# pico_test_synth1.net
KiCad netlist of a schematic drawn in EAGLE
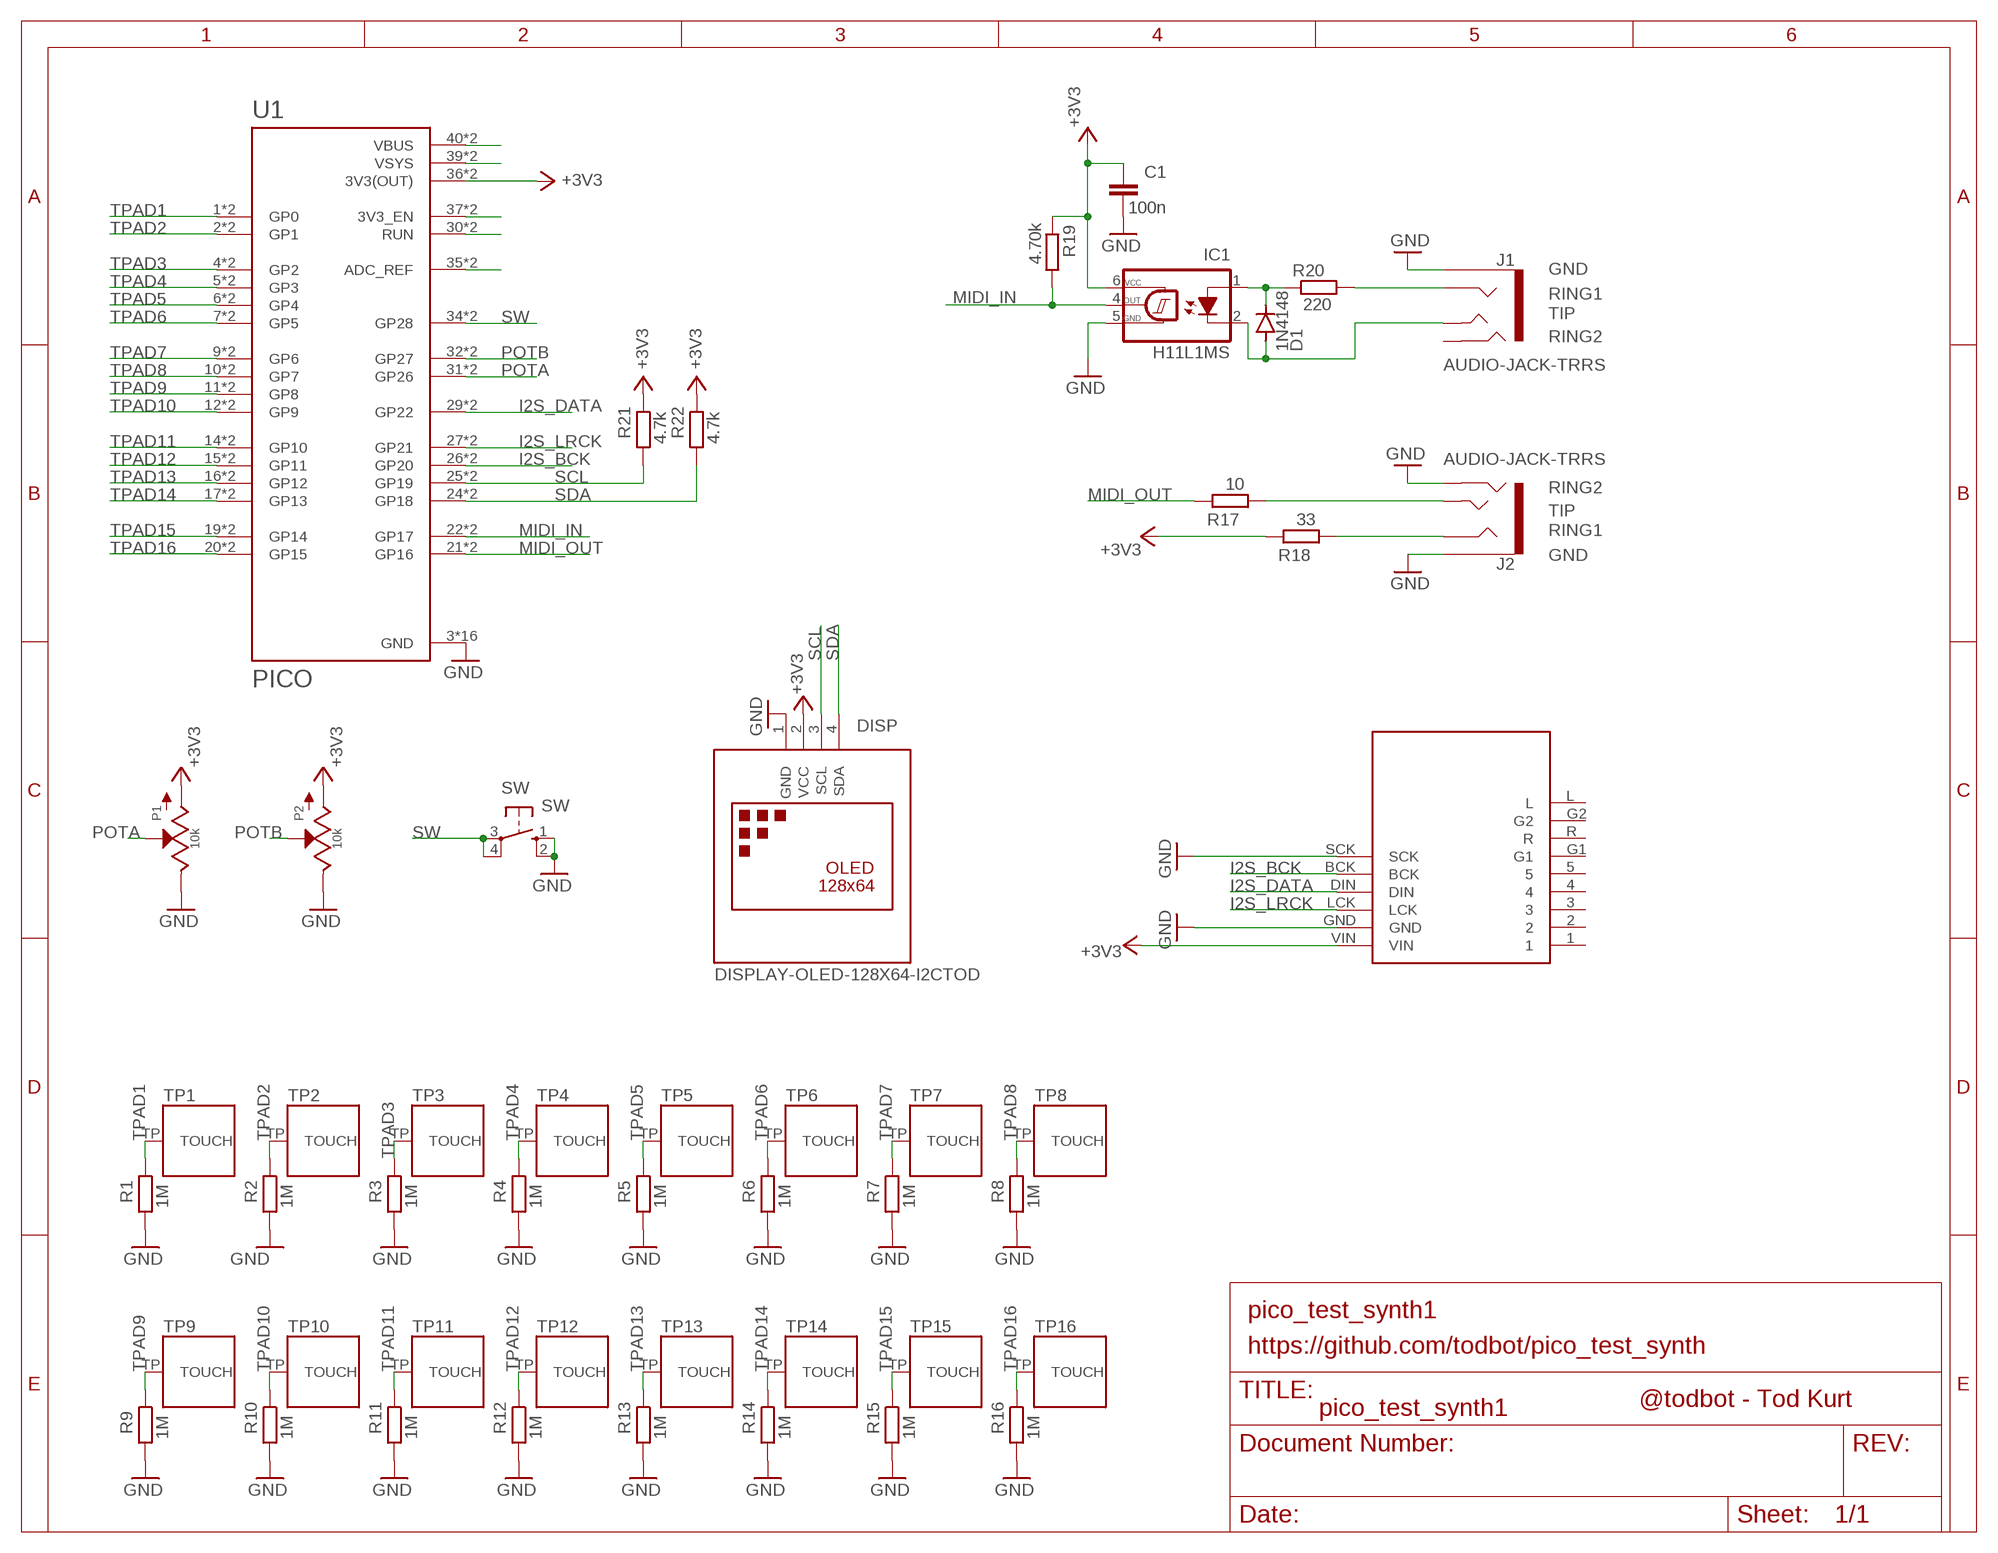
[diagram p0: schematic, sheet 1]

(export (version "E")
  (design (tool "Eeschema 10.0.6"))
  (components
    (comp (ref "C1")
      (value "100n")
      (footprint "eagle-import:C0805")
      (libsource (lib "eagle-import") (part "C-EUC0805"))
    )
    (comp (ref "D1")
      (value "1N4148")
      (footprint "eagle-import:SOD123")
      (libsource (lib "eagle-import") (part "DIODE-SOD123"))
    )
    (comp (ref "DISP")
      (value "DISPLAY-OLED-128X64-I2CTOD")
      (footprint "eagle-import:DISPLAY-OLED-128X64-I2C-TOD")
      (libsource (lib "eagle-import") (part "DISPLAY-OLED-128X64-I2CTOD"))
    )
    (comp (ref "IC1")
      (value "H11L1MS")
      (footprint "eagle-import:DIL6-SMD")
      (libsource (lib "eagle-import") (part "H11LMS1"))
    )
    (comp (ref "J1")
      (value "AUDIO-JACK-TRRS")
      (footprint "eagle-import:PJ-320D_SPARKFUN")
      (fields (field (name "MPN") "PJ-320D"))
      (libsource (lib "eagle-import") (part "AUDIO-JACK-TRRS"))
    )
    (comp (ref "J2")
      (value "AUDIO-JACK-TRRS")
      (footprint "eagle-import:PJ-320D_SPARKFUN")
      (fields (field (name "MPN") "PJ-320D") (field (name "LCSC") "C431535"))
      (libsource (lib "eagle-import") (part "AUDIO-JACK-TRRS"))
    )
    (comp (ref "P1")
      (value "10k")
      (footprint "eagle-import:OG-POTS_ALPS_POT_VERTICAL_WITHBIGKNOB")
      (libsource (lib "eagle-import") (part "POTZEPHPOT_BIGKNOB"))
    )
    (comp (ref "P2")
      (value "10k")
      (footprint "eagle-import:OG-POTS_ALPS_POT_VERTICAL_WITHBIGKNOB")
      (libsource (lib "eagle-import") (part "POTZEPHPOT_BIGKNOB"))
    )
    (comp (ref "R1")
      (value "1M")
      (footprint "eagle-import:R0805")
      (libsource (lib "eagle-import") (part "R-EU_R0805"))
    )
    (comp (ref "R2")
      (value "1M")
      (footprint "eagle-import:R0805")
      (libsource (lib "eagle-import") (part "R-EU_R0805"))
    )
    (comp (ref "R3")
      (value "1M")
      (footprint "eagle-import:R0805")
      (libsource (lib "eagle-import") (part "R-EU_R0805"))
    )
    (comp (ref "R4")
      (value "1M")
      (footprint "eagle-import:R0805")
      (libsource (lib "eagle-import") (part "R-EU_R0805"))
    )
    (comp (ref "R5")
      (value "1M")
      (footprint "eagle-import:R0805")
      (libsource (lib "eagle-import") (part "R-EU_R0805"))
    )
    (comp (ref "R6")
      (value "1M")
      (footprint "eagle-import:R0805")
      (libsource (lib "eagle-import") (part "R-EU_R0805"))
    )
    (comp (ref "R7")
      (value "1M")
      (footprint "eagle-import:R0805")
      (libsource (lib "eagle-import") (part "R-EU_R0805"))
    )
    (comp (ref "R8")
      (value "1M")
      (footprint "eagle-import:R0805")
      (libsource (lib "eagle-import") (part "R-EU_R0805"))
    )
    (comp (ref "R9")
      (value "1M")
      (footprint "eagle-import:R0805")
      (libsource (lib "eagle-import") (part "R-EU_R0805"))
    )
    (comp (ref "R10")
      (value "1M")
      (footprint "eagle-import:R0805")
      (libsource (lib "eagle-import") (part "R-EU_R0805"))
    )
    (comp (ref "R11")
      (value "1M")
      (footprint "eagle-import:R0805")
      (libsource (lib "eagle-import") (part "R-EU_R0805"))
    )
    (comp (ref "R12")
      (value "1M")
      (footprint "eagle-import:R0805")
      (libsource (lib "eagle-import") (part "R-EU_R0805"))
    )
    (comp (ref "R13")
      (value "1M")
      (footprint "eagle-import:R0805")
      (libsource (lib "eagle-import") (part "R-EU_R0805"))
    )
    (comp (ref "R14")
      (value "1M")
      (footprint "eagle-import:R0805")
      (libsource (lib "eagle-import") (part "R-EU_R0805"))
    )
    (comp (ref "R15")
      (value "1M")
      (footprint "eagle-import:R0805")
      (libsource (lib "eagle-import") (part "R-EU_R0805"))
    )
    (comp (ref "R16")
      (value "1M")
      (footprint "eagle-import:R0805")
      (libsource (lib "eagle-import") (part "R-EU_R0805"))
    )
    (comp (ref "R17")
      (value "10")
      (footprint "eagle-import:R0805")
      (libsource (lib "eagle-import") (part "R-EU_R0805"))
    )
    (comp (ref "R18")
      (value "33")
      (footprint "eagle-import:R0805")
      (libsource (lib "eagle-import") (part "R-EU_R0805"))
    )
    (comp (ref "R19")
      (value "4.70k")
      (footprint "eagle-import:R0805")
      (libsource (lib "eagle-import") (part "R-EU_R0805"))
    )
    (comp (ref "R20")
      (value "220")
      (footprint "eagle-import:R0805")
      (libsource (lib "eagle-import") (part "R-EU_R0805"))
    )
    (comp (ref "R21")
      (value "4.7k")
      (footprint "eagle-import:R0805")
      (libsource (lib "eagle-import") (part "R-EU_R0805"))
    )
    (comp (ref "R22")
      (value "4.7k")
      (footprint "eagle-import:R0805")
      (libsource (lib "eagle-import") (part "R-EU_R0805"))
    )
    (comp (ref "SW")
      (value "SW")
      (footprint "eagle-import:B3F-10XX")
      (fields (field (name "MPN") "B3F-1000"))
      (libsource (lib "eagle-import") (part "10-XX"))
    )
    (comp (ref "TP1")
      (value "TOUCHPADA")
      (footprint "eagle-import:TOUCHPADA_0.5IN")
      (libsource (lib "eagle-import") (part "TOUCHPADA"))
    )
    (comp (ref "TP2")
      (value "TOUCHPADA")
      (footprint "eagle-import:TOUCHPADA_0.5IN")
      (libsource (lib "eagle-import") (part "TOUCHPADA"))
    )
    (comp (ref "TP3")
      (value "TOUCHPADA")
      (footprint "eagle-import:TOUCHPADA_0.5IN")
      (libsource (lib "eagle-import") (part "TOUCHPADA"))
    )
    (comp (ref "TP4")
      (value "TOUCHPADA")
      (footprint "eagle-import:TOUCHPADA_0.5IN")
      (libsource (lib "eagle-import") (part "TOUCHPADA"))
    )
    (comp (ref "TP5")
      (value "TOUCHPADA")
      (footprint "eagle-import:TOUCHPADA_0.5IN")
      (libsource (lib "eagle-import") (part "TOUCHPADA"))
    )
    (comp (ref "TP6")
      (value "TOUCHPADA")
      (footprint "eagle-import:TOUCHPADA_0.5IN")
      (libsource (lib "eagle-import") (part "TOUCHPADA"))
    )
    (comp (ref "TP7")
      (value "TOUCHPADA")
      (footprint "eagle-import:TOUCHPADA_0.5IN")
      (libsource (lib "eagle-import") (part "TOUCHPADA"))
    )
    (comp (ref "TP8")
      (value "TOUCHPADA")
      (footprint "eagle-import:TOUCHPADA_0.5IN")
      (libsource (lib "eagle-import") (part "TOUCHPADA"))
    )
    (comp (ref "TP9")
      (value "TOUCHPADA")
      (footprint "eagle-import:TOUCHPADA_0.5IN")
      (libsource (lib "eagle-import") (part "TOUCHPADA"))
    )
    (comp (ref "TP10")
      (value "TOUCHPADA")
      (footprint "eagle-import:TOUCHPADA_0.5IN")
      (libsource (lib "eagle-import") (part "TOUCHPADA"))
    )
    (comp (ref "TP11")
      (value "TOUCHPADA")
      (footprint "eagle-import:TOUCHPADA_0.5IN")
      (libsource (lib "eagle-import") (part "TOUCHPADA"))
    )
    (comp (ref "TP12")
      (value "TOUCHPADA")
      (footprint "eagle-import:TOUCHPADA_0.5IN")
      (libsource (lib "eagle-import") (part "TOUCHPADA"))
    )
    (comp (ref "TP13")
      (value "TOUCHPADA")
      (footprint "eagle-import:TOUCHPADA_0.5IN")
      (libsource (lib "eagle-import") (part "TOUCHPADA"))
    )
    (comp (ref "TP14")
      (value "TOUCHPADA")
      (footprint "eagle-import:TOUCHPADA_0.5IN")
      (libsource (lib "eagle-import") (part "TOUCHPADA"))
    )
    (comp (ref "TP15")
      (value "TOUCHPADA")
      (footprint "eagle-import:TOUCHPADA_0.5IN")
      (libsource (lib "eagle-import") (part "TOUCHPADA"))
    )
    (comp (ref "TP16")
      (value "TOUCHPADA")
      (footprint "eagle-import:TOUCHPADA_0.5IN")
      (libsource (lib "eagle-import") (part "TOUCHPADA"))
    )
    (comp (ref "U1")
      (value "PICO")
      (footprint "eagle-import:PICO-PKG-NO_DEBUG")
      (libsource (lib "eagle-import") (part "RASPBERRY_PICO-NO_DEBUG"))
    )
    (comp (ref "U2")
      (value "I2S_PCM_51XX_SOUNDCARD")
      (footprint "eagle-import:I2S_PCM_5100_SOUNDCARD")
      (libsource (lib "eagle-import") (part "I2S_PCM_51XX_SOUNDCARD"))
    )
  )
  (nets
    (net (code "1") (name "+3V3") (class "Default")
      (node (ref "C1") (pin "1") (pinfunction "1_1") (pintype "passive"))
      (node (ref "DISP") (pin "2") (pinfunction "VCC_2") (pintype "power_in"))
      (node (ref "IC1") (pin "6") (pinfunction "VCC_6") (pintype "power_in"))
      (node (ref "P1") (pin "P$3") (pinfunction "A_P$3") (pintype "passive"))
      (node (ref "P2") (pin "P$3") (pinfunction "A_P$3") (pintype "passive"))
      (node (ref "R18") (pin "1") (pinfunction "1_1") (pintype "passive"))
      (node (ref "R19") (pin "1") (pinfunction "1_1") (pintype "passive"))
      (node (ref "R21") (pin "1") (pinfunction "1_1") (pintype "passive"))
      (node (ref "R22") (pin "1") (pinfunction "1_1") (pintype "passive"))
      (node (ref "U1") (pin "36") (pinfunction "3V3(OUT)_36") (pintype "power_in"))
      (node (ref "U1") (pin "P$36") (pinfunction "3V3(OUT)_P$36") (pintype "power_in"))
      (node (ref "U2") (pin "VIN") (pinfunction "VIN_VIN") (pintype "bidirectional"))
    )
    (net (code "2") (name "/I2S_BCK") (class "Default")
      (node (ref "U1") (pin "26") (pinfunction "GP20_26") (pintype "bidirectional"))
      (node (ref "U1") (pin "P$26") (pinfunction "GP20_P$26") (pintype "bidirectional"))
      (node (ref "U2") (pin "BCK") (pinfunction "BCK_BCK") (pintype "bidirectional"))
    )
    (net (code "3") (name "/I2S_DATA") (class "Default")
      (node (ref "U1") (pin "29") (pinfunction "GP22_29") (pintype "bidirectional"))
      (node (ref "U1") (pin "P$29") (pinfunction "GP22_P$29") (pintype "bidirectional"))
      (node (ref "U2") (pin "DIN") (pinfunction "DIN_DIN") (pintype "bidirectional"))
    )
    (net (code "4") (name "/I2S_LRCK") (class "Default")
      (node (ref "U1") (pin "27") (pinfunction "GP21_27") (pintype "bidirectional"))
      (node (ref "U1") (pin "P$27") (pinfunction "GP21_P$27") (pintype "bidirectional"))
      (node (ref "U2") (pin "LCK") (pinfunction "LCK_LCK") (pintype "bidirectional"))
    )
    (net (code "5") (name "/MIDI_IN") (class "Default")
      (node (ref "IC1") (pin "4") (pinfunction "OUT_4") (pintype "output"))
      (node (ref "R19") (pin "2") (pinfunction "2_2") (pintype "passive"))
      (node (ref "U1") (pin "22") (pinfunction "GP17_22") (pintype "bidirectional"))
      (node (ref "U1") (pin "P$22") (pinfunction "GP17_P$22") (pintype "bidirectional"))
    )
    (net (code "6") (name "/MIDI_OUT") (class "Default")
      (node (ref "R17") (pin "1") (pinfunction "1_1") (pintype "passive"))
      (node (ref "U1") (pin "21") (pinfunction "GP16_21") (pintype "bidirectional"))
      (node (ref "U1") (pin "P$21") (pinfunction "GP16_P$21") (pintype "bidirectional"))
    )
    (net (code "7") (name "/POTA") (class "Default")
      (node (ref "P1") (pin "P$2") (pinfunction "S_P$2") (pintype "passive"))
      (node (ref "U1") (pin "31") (pinfunction "GP26_31") (pintype "bidirectional"))
      (node (ref "U1") (pin "P$31") (pinfunction "GP26_P$31") (pintype "bidirectional"))
    )
    (net (code "8") (name "/POTB") (class "Default")
      (node (ref "P2") (pin "P$2") (pinfunction "S_P$2") (pintype "passive"))
      (node (ref "U1") (pin "32") (pinfunction "GP27_32") (pintype "bidirectional"))
      (node (ref "U1") (pin "P$32") (pinfunction "GP27_P$32") (pintype "bidirectional"))
    )
    (net (code "9") (name "/SCL") (class "Default")
      (node (ref "DISP") (pin "3") (pinfunction "SCL_3") (pintype "bidirectional"))
      (node (ref "R21") (pin "2") (pinfunction "2_2") (pintype "passive"))
      (node (ref "U1") (pin "25") (pinfunction "GP19_25") (pintype "bidirectional"))
      (node (ref "U1") (pin "P$25") (pinfunction "GP19_P$25") (pintype "bidirectional"))
    )
    (net (code "10") (name "/SDA") (class "Default")
      (node (ref "DISP") (pin "4") (pinfunction "SDA_4") (pintype "bidirectional"))
      (node (ref "R22") (pin "2") (pinfunction "2_2") (pintype "passive"))
      (node (ref "U1") (pin "24") (pinfunction "GP18_24") (pintype "bidirectional"))
      (node (ref "U1") (pin "P$24") (pinfunction "GP18_P$24") (pintype "bidirectional"))
    )
    (net (code "11") (name "/SW") (class "Default")
      (node (ref "SW") (pin "3") (pinfunction "P_3") (pintype "passive"))
      (node (ref "SW") (pin "4") (pinfunction "P1_4") (pintype "passive"))
      (node (ref "U1") (pin "34") (pinfunction "GP28_34") (pintype "bidirectional"))
      (node (ref "U1") (pin "P$34") (pinfunction "GP28_P$34") (pintype "bidirectional"))
    )
    (net (code "12") (name "/TPAD1") (class "Default")
      (node (ref "R1") (pin "1") (pinfunction "1_1") (pintype "passive"))
      (node (ref "TP1") (pin "TP") (pinfunction "TOUCH_TP") (pintype "bidirectional"))
      (node (ref "U1") (pin "1") (pinfunction "GP0_1") (pintype "bidirectional"))
      (node (ref "U1") (pin "P$1") (pinfunction "GP0_P$1") (pintype "bidirectional"))
    )
    (net (code "13") (name "/TPAD2") (class "Default")
      (node (ref "R2") (pin "1") (pinfunction "1_1") (pintype "passive"))
      (node (ref "TP2") (pin "TP") (pinfunction "TOUCH_TP") (pintype "bidirectional"))
      (node (ref "U1") (pin "2") (pinfunction "GP1_2") (pintype "bidirectional"))
      (node (ref "U1") (pin "P$2") (pinfunction "GP1_P$2") (pintype "bidirectional"))
    )
    (net (code "14") (name "/TPAD3") (class "Default")
      (node (ref "R3") (pin "1") (pinfunction "1_1") (pintype "passive"))
      (node (ref "TP3") (pin "TP") (pinfunction "TOUCH_TP") (pintype "bidirectional"))
      (node (ref "U1") (pin "4") (pinfunction "GP2_4") (pintype "bidirectional"))
      (node (ref "U1") (pin "P$4") (pinfunction "GP2_P$4") (pintype "bidirectional"))
    )
    (net (code "15") (name "/TPAD4") (class "Default")
      (node (ref "R4") (pin "1") (pinfunction "1_1") (pintype "passive"))
      (node (ref "TP4") (pin "TP") (pinfunction "TOUCH_TP") (pintype "bidirectional"))
      (node (ref "U1") (pin "5") (pinfunction "GP3_5") (pintype "bidirectional"))
      (node (ref "U1") (pin "P$5") (pinfunction "GP3_P$5") (pintype "bidirectional"))
    )
    (net (code "16") (name "/TPAD5") (class "Default")
      (node (ref "R5") (pin "1") (pinfunction "1_1") (pintype "passive"))
      (node (ref "TP5") (pin "TP") (pinfunction "TOUCH_TP") (pintype "bidirectional"))
      (node (ref "U1") (pin "6") (pinfunction "GP4_6") (pintype "bidirectional"))
      (node (ref "U1") (pin "P$6") (pinfunction "GP4_P$6") (pintype "bidirectional"))
    )
    (net (code "17") (name "/TPAD6") (class "Default")
      (node (ref "R6") (pin "1") (pinfunction "1_1") (pintype "passive"))
      (node (ref "TP6") (pin "TP") (pinfunction "TOUCH_TP") (pintype "bidirectional"))
      (node (ref "U1") (pin "7") (pinfunction "GP5_7") (pintype "bidirectional"))
      (node (ref "U1") (pin "P$7") (pinfunction "GP5_P$7") (pintype "bidirectional"))
    )
    (net (code "18") (name "/TPAD7") (class "Default")
      (node (ref "R7") (pin "1") (pinfunction "1_1") (pintype "passive"))
      (node (ref "TP7") (pin "TP") (pinfunction "TOUCH_TP") (pintype "bidirectional"))
      (node (ref "U1") (pin "9") (pinfunction "GP6_9") (pintype "bidirectional"))
      (node (ref "U1") (pin "P$9") (pinfunction "GP6_P$9") (pintype "bidirectional"))
    )
    (net (code "19") (name "/TPAD8") (class "Default")
      (node (ref "R8") (pin "1") (pinfunction "1_1") (pintype "passive"))
      (node (ref "TP8") (pin "TP") (pinfunction "TOUCH_TP") (pintype "bidirectional"))
      (node (ref "U1") (pin "10") (pinfunction "GP7_10") (pintype "bidirectional"))
      (node (ref "U1") (pin "P$10") (pinfunction "GP7_P$10") (pintype "bidirectional"))
    )
    (net (code "20") (name "/TPAD9") (class "Default")
      (node (ref "R9") (pin "1") (pinfunction "1_1") (pintype "passive"))
      (node (ref "TP9") (pin "TP") (pinfunction "TOUCH_TP") (pintype "bidirectional"))
      (node (ref "U1") (pin "11") (pinfunction "GP8_11") (pintype "bidirectional"))
      (node (ref "U1") (pin "P$11") (pinfunction "GP8_P$11") (pintype "bidirectional"))
    )
    (net (code "21") (name "/TPAD10") (class "Default")
      (node (ref "R10") (pin "1") (pinfunction "1_1") (pintype "passive"))
      (node (ref "TP10") (pin "TP") (pinfunction "TOUCH_TP") (pintype "bidirectional"))
      (node (ref "U1") (pin "12") (pinfunction "GP9_12") (pintype "bidirectional"))
      (node (ref "U1") (pin "P$12") (pinfunction "GP9_P$12") (pintype "bidirectional"))
    )
    (net (code "22") (name "/TPAD11") (class "Default")
      (node (ref "R11") (pin "1") (pinfunction "1_1") (pintype "passive"))
      (node (ref "TP11") (pin "TP") (pinfunction "TOUCH_TP") (pintype "bidirectional"))
      (node (ref "U1") (pin "14") (pinfunction "GP10_14") (pintype "bidirectional"))
      (node (ref "U1") (pin "P$14") (pinfunction "GP10_P$14") (pintype "bidirectional"))
    )
    (net (code "23") (name "/TPAD12") (class "Default")
      (node (ref "R12") (pin "1") (pinfunction "1_1") (pintype "passive"))
      (node (ref "TP12") (pin "TP") (pinfunction "TOUCH_TP") (pintype "bidirectional"))
      (node (ref "U1") (pin "15") (pinfunction "GP11_15") (pintype "bidirectional"))
      (node (ref "U1") (pin "P$15") (pinfunction "GP11_P$15") (pintype "bidirectional"))
    )
    (net (code "24") (name "/TPAD13") (class "Default")
      (node (ref "R13") (pin "1") (pinfunction "1_1") (pintype "passive"))
      (node (ref "TP13") (pin "TP") (pinfunction "TOUCH_TP") (pintype "bidirectional"))
      (node (ref "U1") (pin "16") (pinfunction "GP12_16") (pintype "bidirectional"))
      (node (ref "U1") (pin "P$16") (pinfunction "GP12_P$16") (pintype "bidirectional"))
    )
    (net (code "25") (name "/TPAD14") (class "Default")
      (node (ref "R14") (pin "1") (pinfunction "1_1") (pintype "passive"))
      (node (ref "TP14") (pin "TP") (pinfunction "TOUCH_TP") (pintype "bidirectional"))
      (node (ref "U1") (pin "17") (pinfunction "GP13_17") (pintype "bidirectional"))
      (node (ref "U1") (pin "P$17") (pinfunction "GP13_P$17") (pintype "bidirectional"))
    )
    (net (code "26") (name "/TPAD15") (class "Default")
      (node (ref "R15") (pin "1") (pinfunction "1_1") (pintype "passive"))
      (node (ref "TP15") (pin "TP") (pinfunction "TOUCH_TP") (pintype "bidirectional"))
      (node (ref "U1") (pin "19") (pinfunction "GP14_19") (pintype "bidirectional"))
      (node (ref "U1") (pin "P$19") (pinfunction "GP14_P$19") (pintype "bidirectional"))
    )
    (net (code "27") (name "/TPAD16") (class "Default")
      (node (ref "R16") (pin "1") (pinfunction "1_1") (pintype "passive"))
      (node (ref "TP16") (pin "TP") (pinfunction "TOUCH_TP") (pintype "bidirectional"))
      (node (ref "U1") (pin "20") (pinfunction "GP15_20") (pintype "bidirectional"))
      (node (ref "U1") (pin "P$20") (pinfunction "GP15_P$20") (pintype "bidirectional"))
    )
    (net (code "28") (name "GND") (class "Default")
      (node (ref "C1") (pin "2") (pinfunction "2_2") (pintype "passive"))
      (node (ref "DISP") (pin "1") (pinfunction "GND_1") (pintype "power_in"))
      (node (ref "IC1") (pin "5") (pinfunction "GND_5") (pintype "power_in"))
      (node (ref "J1") (pin "EARTH") (pinfunction "EARTH_EARTH") (pintype "bidirectional"))
      (node (ref "J2") (pin "EARTH") (pinfunction "EARTH_EARTH") (pintype "bidirectional"))
      (node (ref "J2") (pin "RING2") (pinfunction "RING2_RING2") (pintype "bidirectional"))
      (node (ref "P1") (pin "P$1") (pinfunction "E_P$1") (pintype "passive"))
      (node (ref "P2") (pin "P$1") (pinfunction "E_P$1") (pintype "passive"))
      (node (ref "R1") (pin "2") (pinfunction "2_2") (pintype "passive"))
      (node (ref "R10") (pin "2") (pinfunction "2_2") (pintype "passive"))
      (node (ref "R11") (pin "2") (pinfunction "2_2") (pintype "passive"))
      (node (ref "R12") (pin "2") (pinfunction "2_2") (pintype "passive"))
      (node (ref "R13") (pin "2") (pinfunction "2_2") (pintype "passive"))
      (node (ref "R14") (pin "2") (pinfunction "2_2") (pintype "passive"))
      (node (ref "R15") (pin "2") (pinfunction "2_2") (pintype "passive"))
      (node (ref "R16") (pin "2") (pinfunction "2_2") (pintype "passive"))
      (node (ref "R2") (pin "2") (pinfunction "2_2") (pintype "passive"))
      (node (ref "R3") (pin "2") (pinfunction "2_2") (pintype "passive"))
      (node (ref "R4") (pin "2") (pinfunction "2_2") (pintype "passive"))
      (node (ref "R5") (pin "2") (pinfunction "2_2") (pintype "passive"))
      (node (ref "R6") (pin "2") (pinfunction "2_2") (pintype "passive"))
      (node (ref "R7") (pin "2") (pinfunction "2_2") (pintype "passive"))
      (node (ref "R8") (pin "2") (pinfunction "2_2") (pintype "passive"))
      (node (ref "R9") (pin "2") (pinfunction "2_2") (pintype "passive"))
      (node (ref "SW") (pin "1") (pinfunction "S_1") (pintype "passive"))
      (node (ref "SW") (pin "2") (pinfunction "S1_2") (pintype "passive"))
      (node (ref "U1") (pin "13") (pinfunction "GND_13") (pintype "power_in"))
      (node (ref "U1") (pin "18") (pinfunction "GND_18") (pintype "power_in"))
      (node (ref "U1") (pin "23") (pinfunction "GND_23") (pintype "power_in"))
      (node (ref "U1") (pin "28") (pinfunction "GND_28") (pintype "power_in"))
      (node (ref "U1") (pin "3") (pinfunction "GND_3") (pintype "power_in"))
      (node (ref "U1") (pin "33") (pinfunction "GND_33") (pintype "power_in"))
      (node (ref "U1") (pin "38") (pinfunction "GND_38") (pintype "power_in"))
      (node (ref "U1") (pin "8") (pinfunction "GND_8") (pintype "power_in"))
      (node (ref "U1") (pin "P$13") (pinfunction "GND_P$13") (pintype "power_in"))
      (node (ref "U1") (pin "P$18") (pinfunction "GND_P$18") (pintype "power_in"))
      (node (ref "U1") (pin "P$23") (pinfunction "GND_P$23") (pintype "power_in"))
      (node (ref "U1") (pin "P$28") (pinfunction "GND_P$28") (pintype "power_in"))
      (node (ref "U1") (pin "P$3") (pinfunction "GND_P$3") (pintype "power_in"))
      (node (ref "U1") (pin "P$33") (pinfunction "GND_P$33") (pintype "power_in"))
      (node (ref "U1") (pin "P$38") (pinfunction "GND_P$38") (pintype "power_in"))
      (node (ref "U1") (pin "P$8") (pinfunction "GND_P$8") (pintype "power_in"))
      (node (ref "U2") (pin "GND") (pinfunction "GND_GND") (pintype "bidirectional"))
      (node (ref "U2") (pin "SCK") (pinfunction "SCK_SCK") (pintype "bidirectional"))
    )
    (net (code "29") (name "Net-(IC1-A)") (class "Default")
      (node (ref "D1") (pin "C") (pinfunction "C_C") (pintype "passive"))
      (node (ref "IC1") (pin "1") (pinfunction "A_1") (pintype "passive"))
      (node (ref "R20") (pin "1") (pinfunction "1_1") (pintype "passive"))
    )
    (net (code "30") (name "Net-(IC1-C)") (class "Default")
      (node (ref "D1") (pin "A") (pinfunction "A_A") (pintype "passive"))
      (node (ref "IC1") (pin "2") (pinfunction "C_2") (pintype "passive"))
      (node (ref "J1") (pin "TIP") (pinfunction "TIP_TIP") (pintype "bidirectional"))
    )
    (net (code "31") (name "Net-(J1-PadRING1)") (class "Default")
      (node (ref "J1") (pin "RING1") (pinfunction "RING1_RING1") (pintype "bidirectional"))
      (node (ref "R20") (pin "2") (pinfunction "2_2") (pintype "passive"))
    )
    (net (code "32") (name "Net-(J2-PadRING1)") (class "Default")
      (node (ref "J2") (pin "RING1") (pinfunction "RING1_RING1") (pintype "bidirectional"))
      (node (ref "R18") (pin "2") (pinfunction "2_2") (pintype "passive"))
    )
    (net (code "33") (name "Net-(J2-PadTIP)") (class "Default")
      (node (ref "J2") (pin "TIP") (pinfunction "TIP_TIP") (pintype "bidirectional"))
      (node (ref "R17") (pin "2") (pinfunction "2_2") (pintype "passive"))
    )
    (net (code "34") (name "Net-(U1-3V3_EN-Pad37)") (class "Default")
      (node (ref "U1") (pin "37") (pinfunction "3V3_EN_37") (pintype "input"))
      (node (ref "U1") (pin "P$37") (pinfunction "3V3_EN_P$37") (pintype "input"))
    )
    (net (code "35") (name "Net-(U1-ADC_REF-Pad35)") (class "Default")
      (node (ref "U1") (pin "35") (pinfunction "ADC_REF_35") (pintype "input"))
      (node (ref "U1") (pin "P$35") (pinfunction "ADC_REF_P$35") (pintype "input"))
    )
    (net (code "36") (name "Net-(U1-RUN-Pad30)") (class "Default")
      (node (ref "U1") (pin "30") (pinfunction "RUN_30") (pintype "input"))
      (node (ref "U1") (pin "P$30") (pinfunction "RUN_P$30") (pintype "input"))
    )
    (net (code "37") (name "Net-(U1-VBUS-Pad40)") (class "Default")
      (node (ref "U1") (pin "40") (pinfunction "VBUS_40") (pintype "power_in"))
      (node (ref "U1") (pin "P$40") (pinfunction "VBUS_P$40") (pintype "power_in"))
    )
    (net (code "38") (name "Net-(U1-VSYS-Pad39)") (class "Default")
      (node (ref "U1") (pin "39") (pinfunction "VSYS_39") (pintype "power_in"))
      (node (ref "U1") (pin "P$39") (pinfunction "VSYS_P$39") (pintype "power_in"))
    )
    (net (code "39") (name "unconnected-(J1-PadRING2)") (class "Default")
      (node (ref "J1") (pin "RING2") (pinfunction "RING2_RING2") (pintype "bidirectional"))
    )
    (net (code "40") (name "unconnected-(U2-Pad1)") (class "Default")
      (node (ref "U2") (pin "1") (pinfunction "1_1") (pintype "bidirectional"))
    )
    (net (code "41") (name "unconnected-(U2-Pad2)") (class "Default")
      (node (ref "U2") (pin "2") (pinfunction "2_2") (pintype "bidirectional"))
    )
    (net (code "42") (name "unconnected-(U2-Pad3)") (class "Default")
      (node (ref "U2") (pin "3") (pinfunction "3_3") (pintype "bidirectional"))
    )
    (net (code "43") (name "unconnected-(U2-Pad4)") (class "Default")
      (node (ref "U2") (pin "4") (pinfunction "4_4") (pintype "bidirectional"))
    )
    (net (code "44") (name "unconnected-(U2-Pad5)") (class "Default")
      (node (ref "U2") (pin "5") (pinfunction "5_5") (pintype "bidirectional"))
    )
    (net (code "45") (name "unconnected-(U2-PadG1)") (class "Default")
      (node (ref "U2") (pin "G1") (pinfunction "G1_G1") (pintype "bidirectional"))
    )
    (net (code "46") (name "unconnected-(U2-PadG2)") (class "Default")
      (node (ref "U2") (pin "G2") (pinfunction "G2_G2") (pintype "bidirectional"))
    )
    (net (code "47") (name "unconnected-(U2-PadL)") (class "Default")
      (node (ref "U2") (pin "L") (pinfunction "L_L") (pintype "bidirectional"))
    )
    (net (code "48") (name "unconnected-(U2-PadR)") (class "Default")
      (node (ref "U2") (pin "R") (pinfunction "R_R") (pintype "bidirectional"))
    )
  )
)
